# SW6124_A_A_B_C_MCU_SEG.net
KiCad netlist of a schematic drawn in Altium Designer
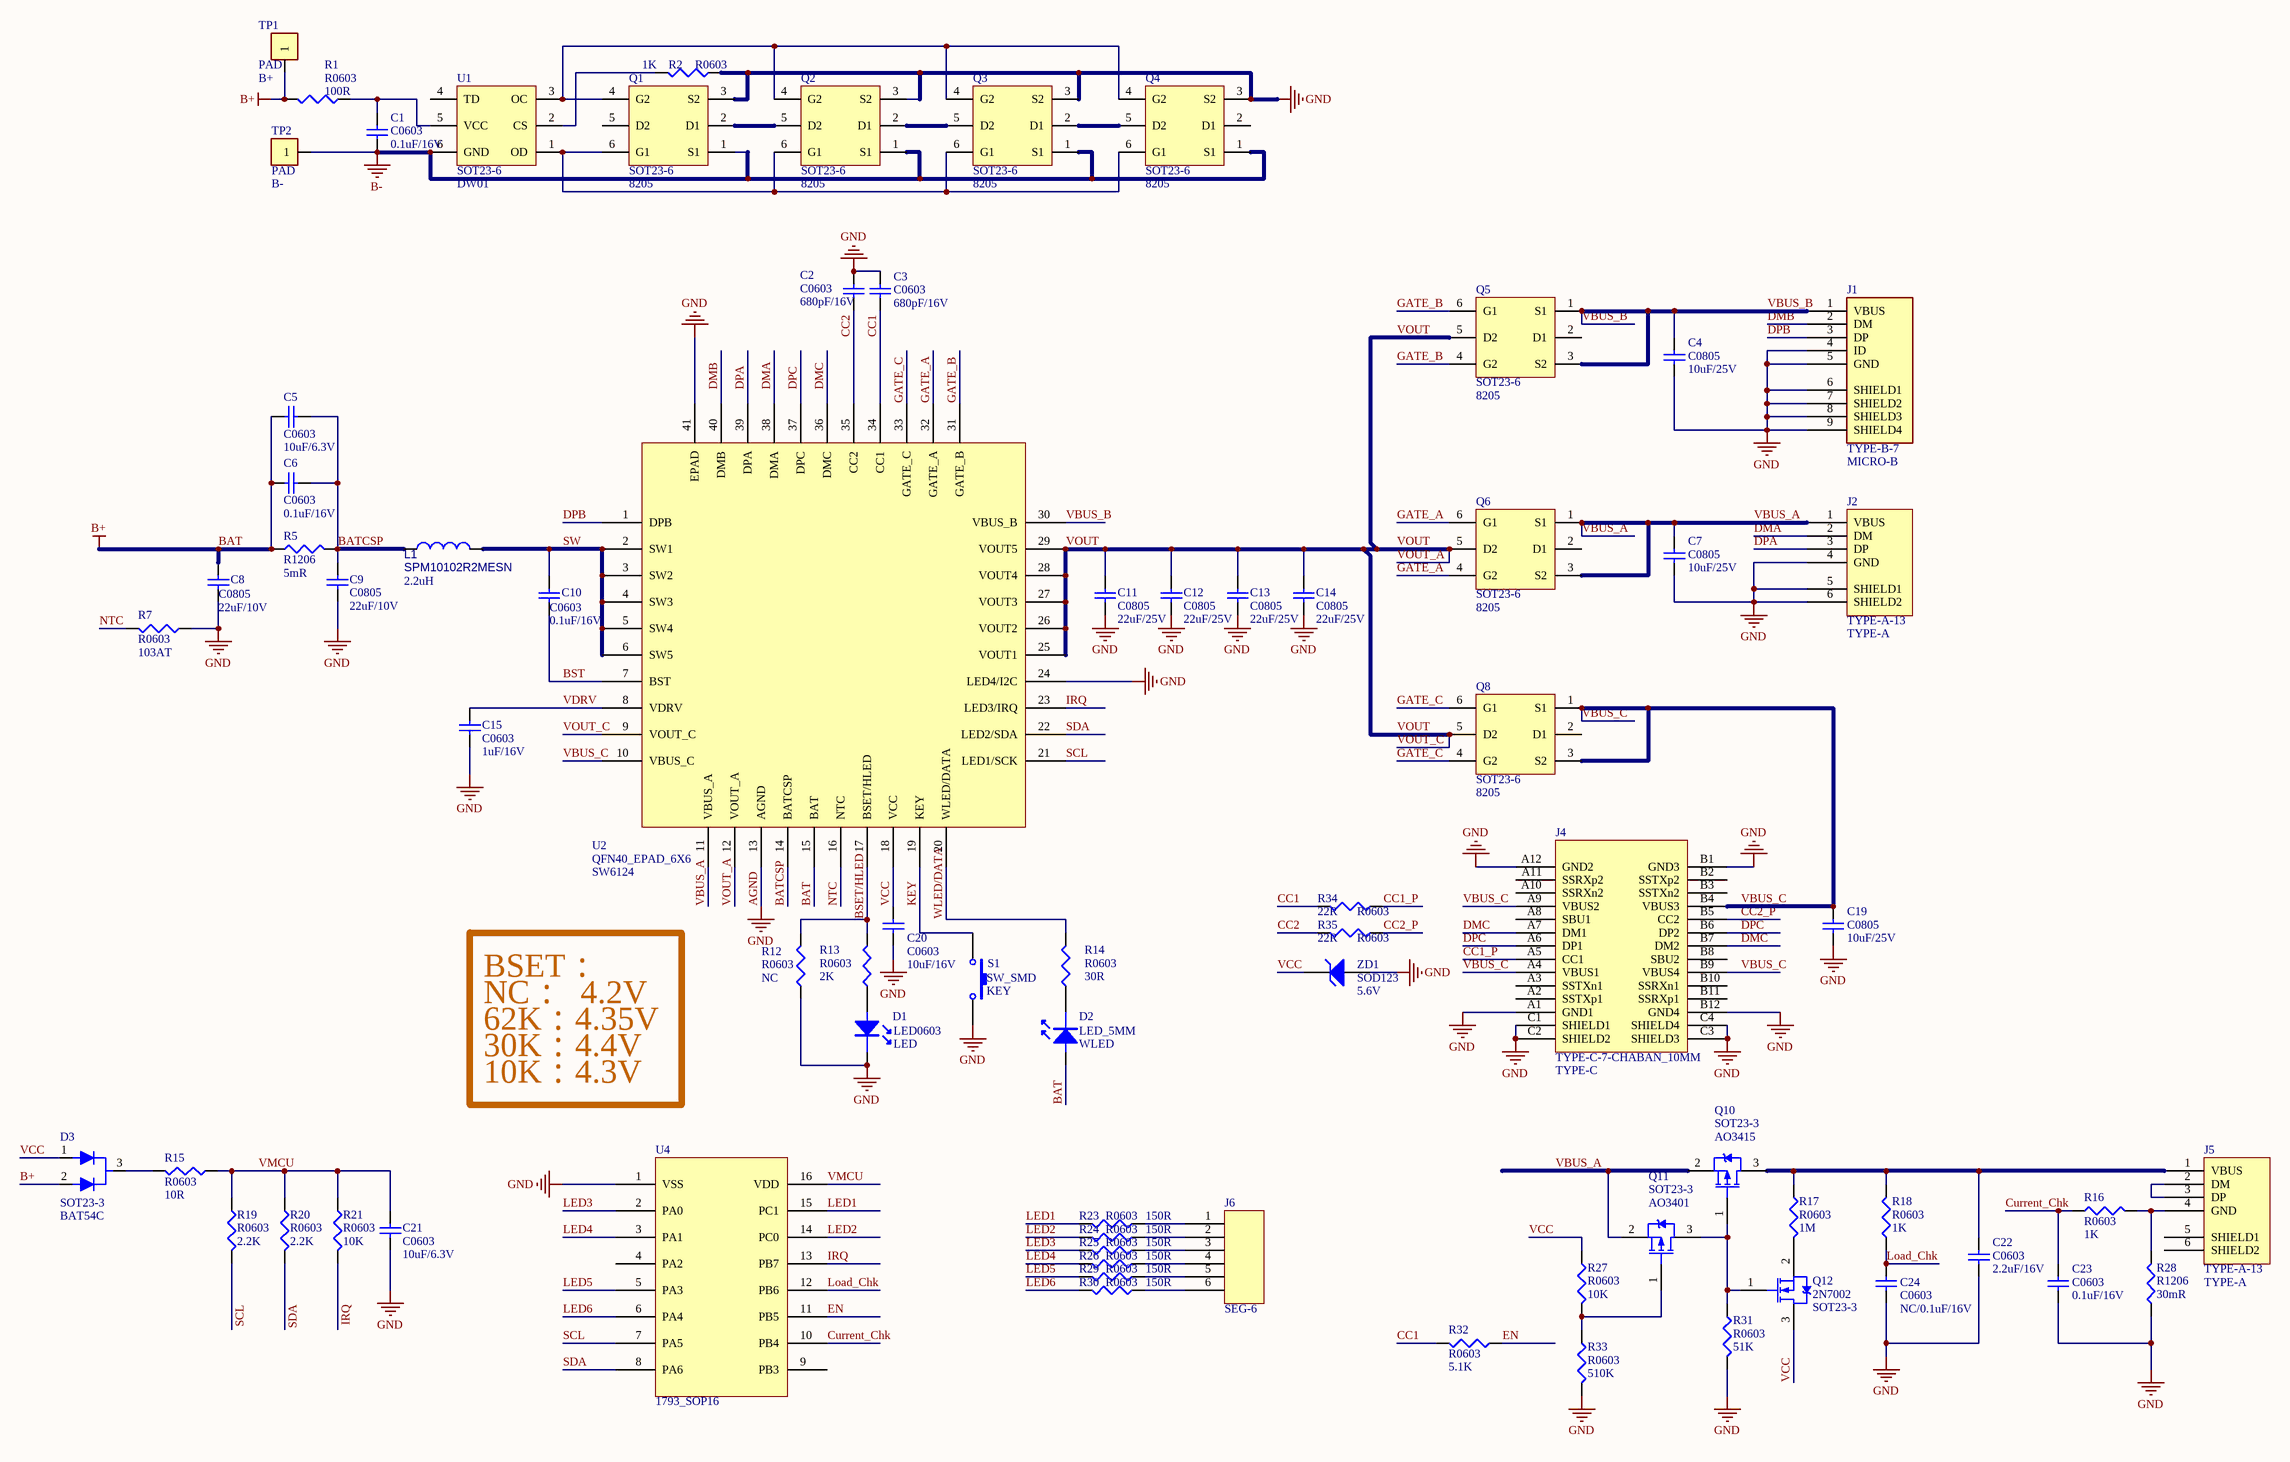
[diagram p0: SW6124+A+A+B+C+MCU+SEG.SchDoc]

(export (version "E")
  (design (tool "Eeschema 10.0.6"))
  (components
    (comp (ref "C1")
      (value "C0603")
      (footprint "C0603")
      (description "Capacitor")
      (fields (field (name "ALTIUM_VALUE") "0.1uF/16V") (field (name "PUBLISHER") "Altium Limited"))
      (libsource (lib "*") (part "Cap"))
    )
    (comp (ref "C2")
      (value "C0603")
      (footprint "C0603")
      (description "Capacitor")
      (fields (field (name "ALTIUM_VALUE") "680pF/16V") (field (name "PUBLISHER") "Altium Limited"))
      (libsource (lib "*") (part "CAP0603"))
    )
    (comp (ref "C3")
      (value "C0603")
      (footprint "C0603")
      (description "Capacitor")
      (fields (field (name "ALTIUM_VALUE") "680pF/16V") (field (name "PUBLISHER") "Altium Limited"))
      (libsource (lib "*") (part "CAP0603"))
    )
    (comp (ref "C4")
      (value "C0805")
      (footprint "C0805")
      (description "Capacitor")
      (fields (field (name "ALTIUM_VALUE") "10uF/25V") (field (name "PUBLISHER") "Altium Limited"))
      (libsource (lib "*") (part "CAP0603"))
    )
    (comp (ref "C5")
      (value "C0603")
      (footprint "C0603")
      (description "Capacitor")
      (fields (field (name "ALTIUM_VALUE") "10uF/6.3V") (field (name "PUBLISHER") "Altium Limited"))
      (libsource (lib "*") (part "CAP0603"))
    )
    (comp (ref "C6")
      (value "C0603")
      (footprint "C0603")
      (description "Capacitor")
      (fields (field (name "ALTIUM_VALUE") "0.1uF/16V") (field (name "PUBLISHER") "Altium Limited"))
      (libsource (lib "*") (part "CAP0603"))
    )
    (comp (ref "C7")
      (value "C0805")
      (footprint "C0805")
      (description "Capacitor")
      (fields (field (name "ALTIUM_VALUE") "10uF/25V") (field (name "PUBLISHER") "Altium Limited"))
      (libsource (lib "*") (part "CAP0603"))
    )
    (comp (ref "C8")
      (value "C0805")
      (footprint "C0805")
      (description "Capacitor")
      (fields (field (name "ALTIUM_VALUE") "22uF/10V") (field (name "PUBLISHER") "Altium Limited"))
      (libsource (lib "*") (part "CAP0805"))
    )
    (comp (ref "C9")
      (value "C0805")
      (footprint "C0805")
      (description "Capacitor")
      (fields (field (name "ALTIUM_VALUE") "22uF/10V") (field (name "PUBLISHER") "Altium Limited"))
      (libsource (lib "*") (part "CAP0805"))
    )
    (comp (ref "C10")
      (value "C0603")
      (footprint "C0603")
      (description "Capacitor")
      (fields (field (name "ALTIUM_VALUE") "0.1uF/16V") (field (name "PUBLISHER") "Altium Limited"))
      (libsource (lib "*") (part "CAP0603"))
    )
    (comp (ref "C11")
      (value "C0805")
      (footprint "C0805")
      (description "Capacitor")
      (fields (field (name "ALTIUM_VALUE") "22uF/25V") (field (name "PUBLISHER") "Altium Limited"))
      (libsource (lib "*") (part "CAP0805"))
    )
    (comp (ref "C12")
      (value "C0805")
      (footprint "C0805")
      (description "Capacitor")
      (fields (field (name "ALTIUM_VALUE") "22uF/25V") (field (name "PUBLISHER") "Altium Limited"))
      (libsource (lib "*") (part "CAP0805"))
    )
    (comp (ref "C13")
      (value "C0805")
      (footprint "C0805")
      (description "Capacitor")
      (fields (field (name "ALTIUM_VALUE") "22uF/25V") (field (name "PUBLISHER") "Altium Limited"))
      (libsource (lib "*") (part "CAP0805"))
    )
    (comp (ref "C14")
      (value "C0805")
      (footprint "C0805")
      (description "Capacitor")
      (fields (field (name "ALTIUM_VALUE") "22uF/25V") (field (name "PUBLISHER") "Altium Limited"))
      (libsource (lib "*") (part "CAP0805"))
    )
    (comp (ref "C15")
      (value "C0603")
      (footprint "C0603")
      (description "Capacitor")
      (fields (field (name "ALTIUM_VALUE") "1uF/16V") (field (name "PUBLISHER") "Altium Limited"))
      (libsource (lib "*") (part "CAP0603"))
    )
    (comp (ref "C19")
      (value "C0805")
      (footprint "C0805")
      (description "Capacitor")
      (fields (field (name "ALTIUM_VALUE") "10uF/25V") (field (name "PUBLISHER") "Altium Limited"))
      (libsource (lib "*") (part "CAP0603"))
    )
    (comp (ref "C20")
      (value "C0603")
      (footprint "C0603")
      (description "Capacitor")
      (fields (field (name "ALTIUM_VALUE") "10uF/16V") (field (name "PUBLISHER") "Altium Limited"))
      (libsource (lib "*") (part "CAP0603"))
    )
    (comp (ref "C21")
      (value "C0603")
      (footprint "C0603")
      (description "Capacitor")
      (fields (field (name "ALTIUM_VALUE") "10uF/6.3V") (field (name "PUBLISHER") "Altium Limited"))
      (libsource (lib "*") (part "CAP0603"))
    )
    (comp (ref "C22")
      (value "C0603")
      (footprint "C0603")
      (description "Capacitor")
      (fields (field (name "ALTIUM_VALUE") "2.2uF/16V") (field (name "PUBLISHER") "Altium Limited"))
      (libsource (lib "*") (part "CAP0603"))
    )
    (comp (ref "C23")
      (value "C0603")
      (footprint "C0603")
      (description "Capacitor")
      (fields (field (name "ALTIUM_VALUE") "0.1uF/16V") (field (name "PUBLISHER") "Altium Limited"))
      (libsource (lib "*") (part "CAP0603"))
    )
    (comp (ref "C24")
      (value "C0603")
      (footprint "C0603")
      (description "Capacitor")
      (fields (field (name "ALTIUM_VALUE") "NC/0.1uF/16V") (field (name "PUBLISHER") "Altium Limited"))
      (libsource (lib "*") (part "CAP0603"))
    )
    (comp (ref "D1") (value "LED") (footprint "LED0603") (libsource (lib "*") (part "LED")))
    (comp (ref "D2")
      (value "WLED")
      (footprint "LED_5MM")
      (fields (field (name "FOOTPRINF") "LED_5MM") (field (name "Comment") "LED_5MM"))
      (libsource (lib "*") (part "LED"))
    )
    (comp (ref "D3") (value "BAT54C") (footprint "SOT23-3") (libsource (lib "Schlib1-2012") (part "D3")))
    (comp (ref "J1")
      (value "MICRO-B")
      (footprint "TYPE-B-7")
      (fields (field (name "FOOTPRINTF") "TYPE-B-7") (field (name "Comment") "USB_MICRO_B"))
      (libsource (lib "*") (part "USB_MICRO_B"))
    )
    (comp (ref "J2")
      (value "TYPE-A")
      (footprint "TYPE-A-13")
      (fields (field (name "FOOTPRINF") "TYPE-A-13") (field (name "Comment") "TYPE-A-1"))
      (libsource (lib "*") (part "TYPE-A-1"))
    )
    (comp (ref "J4")
      (value "TYPE-C")
      (footprint "TYPE-C-7-CHABAN_10MM")
      (libsource (lib "*") (part "TYPE-C"))
    )
    (comp (ref "J5")
      (value "TYPE-A")
      (footprint "PIE10-USB")
      (fields (field (name "FOOTPRINF") "TYPE-A-13") (field (name "Comment") "TYPE-A-1"))
      (libsource (lib "*") (part "TYPE-A-1"))
    )
    (comp (ref "J6") (value "SEG-6") (libsource (lib "TEST") (part "LCD-6")))
    (comp (ref "L1")
      (value "SPM10102R2MESN")
      (footprint "INDUCTOR_SPM1010")
      (fields (field (name "ALTIUM_VALUE") "2.2uH"))
      (libsource (lib "*") (part "INDUCTOR"))
    )
    (comp (ref "Q1")
      (value "8205")
      (footprint "SOT23-6")
      (fields (field (name "FOOTPRINF") "SOT23-6"))
      (libsource (lib "") (part "8205B_1"))
    )
    (comp (ref "Q2")
      (value "8205")
      (footprint "SOT23-6")
      (fields (field (name "FOOTPRINF") "SOT23-6"))
      (libsource (lib "") (part "8205B_1"))
    )
    (comp (ref "Q3")
      (value "8205")
      (footprint "SOT23-6")
      (fields (field (name "FOOTPRINF") "SOT23-6"))
      (libsource (lib "") (part "8205B_1"))
    )
    (comp (ref "Q4")
      (value "8205")
      (footprint "SOT23-6")
      (fields (field (name "FOOTPRINF") "SOT23-6"))
      (libsource (lib "") (part "8205B_1"))
    )
    (comp (ref "Q5")
      (value "8205")
      (footprint "SOT23-6")
      (fields (field (name "FOOTPRINF") "SOT23-6"))
      (libsource (lib "*") (part "8205B"))
    )
    (comp (ref "Q6")
      (value "8205")
      (footprint "SOT23-6")
      (fields (field (name "FOOTPRINF") "SOT23-6"))
      (libsource (lib "*") (part "8205B"))
    )
    (comp (ref "Q8")
      (value "8205")
      (footprint "SOT23-6")
      (fields (field (name "FOOTPRINF") "SOT23-6"))
      (libsource (lib "*") (part "8205B"))
    )
    (comp (ref "Q10")
      (value "AO3415")
      (footprint "SOT23-3")
      (description "P-Channel Power MOSFET")
      (fields (field (name "Comment") "PMOS-2") (field (name "PUBLISHER") "Altium Limited"))
      (libsource (lib "Miscellaneous Devices") (part "PMOS-2"))
    )
    (comp (ref "Q11")
      (value "AO3401")
      (footprint "SOT23-3")
      (description "P-Channel Power MOSFET")
      (fields (field (name "Comment") "PMOS-2") (field (name "PUBLISHER") "Altium Limited"))
      (libsource (lib "Miscellaneous Devices") (part "PMOS-2"))
    )
    (comp (ref "Q12")
      (value "2N7002")
      (footprint "SOT23-3")
      (description "N-Channel Power MOSFET")
      (fields (field (name "Comment") "NMOS-2") (field (name "PUBLISHER") "Altium Limited"))
      (libsource (lib "Miscellaneous Devices") (part "NMOS-2"))
    )
    (comp (ref "R1")
      (value "R0603")
      (footprint "R0603")
      (description "Resistor")
      (fields (field (name "ALTIUM_VALUE") "100R") (field (name "PUBLISHER") "Altium Limited"))
      (libsource (lib "*") (part "Res3"))
    )
    (comp (ref "R2")
      (value "R0603")
      (footprint "R0603")
      (description "Resistor")
      (fields (field (name "ALTIUM_VALUE") "1K") (field (name "PUBLISHER") "Altium Limited"))
      (libsource (lib "*") (part "Res3"))
    )
    (comp (ref "R5")
      (value "R1206")
      (footprint "R1206")
      (description "Resistor")
      (fields (field (name "ALTIUM_VALUE") "5mR") (field (name "PUBLISHER") "Altium Limited"))
      (libsource (lib "*") (part "RES"))
    )
    (comp (ref "R7")
      (value "R0603")
      (footprint "R0603")
      (description "Resistor")
      (fields (field (name "ALTIUM_VALUE") "103AT") (field (name "PUBLISHER") "Altium Limited"))
      (libsource (lib "*") (part "RES"))
    )
    (comp (ref "R12")
      (value "R0603")
      (footprint "R0603")
      (description "Resistor")
      (fields (field (name "ALTIUM_VALUE") "NC") (field (name "PUBLISHER") "Altium Limited"))
      (libsource (lib "*") (part "RES"))
    )
    (comp (ref "R13")
      (value "R0603")
      (footprint "R0603")
      (description "Resistor")
      (fields (field (name "ALTIUM_VALUE") "2K") (field (name "PUBLISHER") "Altium Limited"))
      (libsource (lib "*") (part "RES"))
    )
    (comp (ref "R14")
      (value "R0603")
      (footprint "R0603")
      (description "Resistor")
      (fields (field (name "ALTIUM_VALUE") "30R") (field (name "PUBLISHER") "Altium Limited"))
      (libsource (lib "*") (part "RES"))
    )
    (comp (ref "R15")
      (value "R0603")
      (footprint "R0603")
      (description "Resistor")
      (fields (field (name "ALTIUM_VALUE") "10R") (field (name "PUBLISHER") "Altium Limited"))
      (libsource (lib "*") (part "RES"))
    )
    (comp (ref "R16")
      (value "R0603")
      (footprint "R0603")
      (description "Resistor")
      (fields (field (name "ALTIUM_VALUE") "1K") (field (name "PUBLISHER") "Altium Limited"))
      (libsource (lib "*") (part "RES"))
    )
    (comp (ref "R17")
      (value "R0603")
      (footprint "R0603")
      (description "Resistor")
      (fields (field (name "ALTIUM_VALUE") "1M") (field (name "PUBLISHER") "Altium Limited"))
      (libsource (lib "*") (part "RES"))
    )
    (comp (ref "R18")
      (value "R0603")
      (footprint "R0603")
      (description "Resistor")
      (fields (field (name "ALTIUM_VALUE") "1K") (field (name "PUBLISHER") "Altium Limited"))
      (libsource (lib "*") (part "RES"))
    )
    (comp (ref "R19")
      (value "R0603")
      (footprint "R0603")
      (description "Resistor")
      (fields (field (name "ALTIUM_VALUE") "2.2K") (field (name "PUBLISHER") "Altium Limited"))
      (libsource (lib "*") (part "RES"))
    )
    (comp (ref "R20")
      (value "R0603")
      (footprint "R0603")
      (description "Resistor")
      (fields (field (name "ALTIUM_VALUE") "2.2K") (field (name "PUBLISHER") "Altium Limited"))
      (libsource (lib "*") (part "RES"))
    )
    (comp (ref "R21")
      (value "R0603")
      (footprint "R0603")
      (description "Resistor")
      (fields (field (name "ALTIUM_VALUE") "10K") (field (name "PUBLISHER") "Altium Limited"))
      (libsource (lib "*") (part "RES"))
    )
    (comp (ref "R23")
      (value "R0603")
      (footprint "R0603")
      (description "Resistor")
      (fields (field (name "ALTIUM_VALUE") "150R") (field (name "PUBLISHER") "Altium Limited"))
      (libsource (lib "*") (part "RES"))
    )
    (comp (ref "R24")
      (value "R0603")
      (footprint "R0603")
      (description "Resistor")
      (fields (field (name "ALTIUM_VALUE") "150R") (field (name "PUBLISHER") "Altium Limited"))
      (libsource (lib "*") (part "RES"))
    )
    (comp (ref "R25")
      (value "R0603")
      (footprint "R0603")
      (description "Resistor")
      (fields (field (name "ALTIUM_VALUE") "150R") (field (name "PUBLISHER") "Altium Limited"))
      (libsource (lib "*") (part "RES"))
    )
    (comp (ref "R26")
      (value "R0603")
      (footprint "R0603")
      (description "Resistor")
      (fields (field (name "ALTIUM_VALUE") "150R") (field (name "PUBLISHER") "Altium Limited"))
      (libsource (lib "*") (part "RES"))
    )
    (comp (ref "R27")
      (value "R0603")
      (footprint "R0603")
      (description "Resistor")
      (fields (field (name "ALTIUM_VALUE") "10K") (field (name "PUBLISHER") "Altium Limited"))
      (libsource (lib "*") (part "RES"))
    )
    (comp (ref "R28")
      (value "R1206")
      (footprint "C-1206A")
      (description "Resistor")
      (fields (field (name "ALTIUM_VALUE") "30mR") (field (name "PUBLISHER") "Altium Limited"))
      (libsource (lib "*") (part "RES"))
    )
    (comp (ref "R29")
      (value "R0603")
      (footprint "R0603")
      (description "Resistor")
      (fields (field (name "ALTIUM_VALUE") "150R") (field (name "PUBLISHER") "Altium Limited"))
      (libsource (lib "*") (part "RES"))
    )
    (comp (ref "R30")
      (value "R0603")
      (footprint "R0603")
      (description "Resistor")
      (fields (field (name "ALTIUM_VALUE") "150R") (field (name "PUBLISHER") "Altium Limited"))
      (libsource (lib "*") (part "RES"))
    )
    (comp (ref "R31")
      (value "R0603")
      (footprint "R0603")
      (description "Resistor")
      (fields (field (name "ALTIUM_VALUE") "51K") (field (name "PUBLISHER") "Altium Limited"))
      (libsource (lib "*") (part "RES"))
    )
    (comp (ref "R32")
      (value "R0603")
      (footprint "R0603")
      (description "Resistor")
      (fields (field (name "ALTIUM_VALUE") "5.1K") (field (name "PUBLISHER") "Altium Limited"))
      (libsource (lib "*") (part "RES"))
    )
    (comp (ref "R33")
      (value "R0603")
      (footprint "R0603")
      (description "Resistor")
      (fields (field (name "ALTIUM_VALUE") "510K") (field (name "PUBLISHER") "Altium Limited"))
      (libsource (lib "*") (part "RES"))
    )
    (comp (ref "R34")
      (value "R0603")
      (footprint "R0603")
      (description "Resistor")
      (fields (field (name "ALTIUM_VALUE") "22R") (field (name "PUBLISHER") "Altium Limited"))
      (libsource (lib "*") (part "RES"))
    )
    (comp (ref "R35")
      (value "R0603")
      (footprint "R0603")
      (description "Resistor")
      (fields (field (name "ALTIUM_VALUE") "22R") (field (name "PUBLISHER") "Altium Limited"))
      (libsource (lib "*") (part "RES"))
    )
    (comp (ref "S1")
      (value "KEY")
      (footprint "SW_SMD")
      (fields (field (name "FOOTPRINF") "SW_SMD"))
      (libsource (lib "*") (part "SW K"))
    )
    (comp (ref "TP1") (value "B+") (footprint "PAD") (libsource (lib "") (part "Test Point_1")))
    (comp (ref "TP2") (value "B-") (footprint "PAD") (libsource (lib "*") (part "Test Point")))
    (comp (ref "U1")
      (value "DW01")
      (footprint "SOT23-6")
      (fields (field (name "FOOTPRINF") "SOT23-6"))
      (libsource (lib "*") (part "DW01"))
    )
    (comp (ref "U2")
      (value "SW6124")
      (footprint "QFN40_EPAD_6X6")
      (libsource (lib "TEST") (part "SW6106_AFC"))
    )
    (comp (ref "U4") (value "1793_SOP16") (libsource (lib "TEST") (part "1793_SOP16")))
    (comp (ref "ZD1")
      (value "SOD123")
      (footprint "SOD-123")
      (description "Zener Diode")
      (fields (field (name "ALTIUM_UNNAMED_1") "5.6V"))
      (libsource (lib "Miscellaneous Devices") (part "D Zener"))
    )
  )
  (nets
    (net (code "1") (name "/BATCSP") (class "Default")
      (node (ref "C5") (pin "2") (pinfunction "2_2") (pintype "passive"))
      (node (ref "C6") (pin "2") (pinfunction "2_2") (pintype "passive"))
      (node (ref "C9") (pin "2") (pinfunction "2_2") (pintype "passive"))
      (node (ref "L1") (pin "1") (pinfunction "1_1") (pintype "passive"))
      (node (ref "R5") (pin "2") (pinfunction "2_2") (pintype "passive"))
      (node (ref "U2") (pin "14") (pinfunction "BATCSP_14") (pintype "passive"))
    )
    (net (code "2") (name "/BSET{slash}HLED") (class "Default")
      (node (ref "R12") (pin "2") (pinfunction "2_2") (pintype "passive"))
      (node (ref "R13") (pin "2") (pinfunction "2_2") (pintype "passive"))
      (node (ref "U2") (pin "17") (pinfunction "BSET/HLED_17") (pintype "passive"))
    )
    (net (code "3") (name "/BST") (class "Default")
      (node (ref "C10") (pin "1") (pinfunction "1_1") (pintype "passive"))
      (node (ref "U2") (pin "7") (pinfunction "BST_7") (pintype "passive"))
    )
    (net (code "4") (name "/CC1") (class "Default")
      (node (ref "C3") (pin "1") (pinfunction "1_1") (pintype "passive"))
      (node (ref "R32") (pin "2") (pinfunction "2_2") (pintype "passive"))
      (node (ref "R34") (pin "2") (pinfunction "2_2") (pintype "passive"))
      (node (ref "U2") (pin "34") (pinfunction "CC1_34") (pintype "passive"))
    )
    (net (code "5") (name "/CC1_P") (class "Default")
      (node (ref "J4") (pin "A5") (pinfunction "CC1_A5") (pintype "passive"))
      (node (ref "R34") (pin "1") (pinfunction "1_1") (pintype "passive"))
    )
    (net (code "6") (name "/CC2") (class "Default")
      (node (ref "C2") (pin "1") (pinfunction "1_1") (pintype "passive"))
      (node (ref "R35") (pin "2") (pinfunction "2_2") (pintype "passive"))
      (node (ref "U2") (pin "35") (pinfunction "CC2_35") (pintype "passive"))
    )
    (net (code "7") (name "/CC2_P") (class "Default")
      (node (ref "J4") (pin "B5") (pinfunction "CC2_B5") (pintype "passive"))
      (node (ref "R35") (pin "1") (pinfunction "1_1") (pintype "passive"))
    )
    (net (code "8") (name "/Current_Chk") (class "Default")
      (node (ref "C23") (pin "2") (pinfunction "2_2") (pintype "passive"))
      (node (ref "R16") (pin "1") (pinfunction "1_1") (pintype "passive"))
      (node (ref "U4") (pin "10") (pinfunction "PB4_10") (pintype "passive"))
    )
    (net (code "9") (name "/DMA") (class "Default")
      (node (ref "J2") (pin "2") (pinfunction "DM_2") (pintype "passive"))
      (node (ref "U2") (pin "38") (pinfunction "DMA_38") (pintype "passive"))
    )
    (net (code "10") (name "/DMB") (class "Default")
      (node (ref "J1") (pin "2") (pinfunction "DM_2") (pintype "passive"))
      (node (ref "U2") (pin "40") (pinfunction "DMB_40") (pintype "passive"))
    )
    (net (code "11") (name "/DMC") (class "Default")
      (node (ref "J4") (pin "A7") (pinfunction "DM1_A7") (pintype "passive"))
      (node (ref "J4") (pin "B7") (pinfunction "DM2_B7") (pintype "passive"))
      (node (ref "U2") (pin "36") (pinfunction "DMC_36") (pintype "passive"))
    )
    (net (code "12") (name "/DPA") (class "Default")
      (node (ref "J2") (pin "3") (pinfunction "DP_3") (pintype "passive"))
      (node (ref "U2") (pin "39") (pinfunction "DPA_39") (pintype "passive"))
    )
    (net (code "13") (name "/DPB") (class "Default")
      (node (ref "J1") (pin "3") (pinfunction "DP_3") (pintype "passive"))
      (node (ref "U2") (pin "1") (pinfunction "DPB_1") (pintype "passive"))
    )
    (net (code "14") (name "/DPC") (class "Default")
      (node (ref "J4") (pin "A6") (pinfunction "DP1_A6") (pintype "passive"))
      (node (ref "J4") (pin "B6") (pinfunction "DP2_B6") (pintype "passive"))
      (node (ref "U2") (pin "37") (pinfunction "DPC_37") (pintype "passive"))
    )
    (net (code "15") (name "/EN") (class "Default")
      (node (ref "R32") (pin "1") (pinfunction "1_1") (pintype "passive"))
      (node (ref "U4") (pin "11") (pinfunction "PB5_11") (pintype "passive"))
    )
    (net (code "16") (name "/GATE_A") (class "Default")
      (node (ref "Q6") (pin "4") (pinfunction "G2_4") (pintype "passive"))
      (node (ref "Q6") (pin "6") (pinfunction "G1_6") (pintype "passive"))
      (node (ref "U2") (pin "32") (pinfunction "GATE_A_32") (pintype "passive"))
    )
    (net (code "17") (name "/GATE_B") (class "Default")
      (node (ref "Q5") (pin "4") (pinfunction "G2_4") (pintype "passive"))
      (node (ref "Q5") (pin "6") (pinfunction "G1_6") (pintype "passive"))
      (node (ref "U2") (pin "31") (pinfunction "GATE_B_31") (pintype "passive"))
    )
    (net (code "18") (name "/GATE_C") (class "Default")
      (node (ref "Q8") (pin "4") (pinfunction "G2_4") (pintype "passive"))
      (node (ref "Q8") (pin "6") (pinfunction "G1_6") (pintype "passive"))
      (node (ref "U2") (pin "33") (pinfunction "GATE_C_33") (pintype "passive"))
    )
    (net (code "19") (name "/IRQ") (class "Default")
      (node (ref "R21") (pin "2") (pinfunction "2_2") (pintype "passive"))
      (node (ref "U2") (pin "23") (pinfunction "LED3/IRQ_23") (pintype "passive"))
      (node (ref "U4") (pin "13") (pinfunction "PB7_13") (pintype "passive"))
    )
    (net (code "20") (name "/KEY") (class "Default")
      (node (ref "S1") (pin "1") (pinfunction "1_1") (pintype "passive"))
      (node (ref "U2") (pin "19") (pinfunction "KEY_19") (pintype "passive"))
    )
    (net (code "21") (name "/LED1") (class "Default")
      (node (ref "R23") (pin "2") (pinfunction "2_2") (pintype "passive"))
      (node (ref "U4") (pin "15") (pinfunction "PC1_15") (pintype "passive"))
    )
    (net (code "22") (name "/LED2") (class "Default")
      (node (ref "R24") (pin "2") (pinfunction "2_2") (pintype "passive"))
      (node (ref "U4") (pin "14") (pinfunction "PC0_14") (pintype "passive"))
    )
    (net (code "23") (name "/LED3") (class "Default")
      (node (ref "R25") (pin "2") (pinfunction "2_2") (pintype "passive"))
      (node (ref "U4") (pin "2") (pinfunction "PA0_2") (pintype "passive"))
    )
    (net (code "24") (name "/LED4") (class "Default")
      (node (ref "R26") (pin "2") (pinfunction "2_2") (pintype "passive"))
      (node (ref "U4") (pin "3") (pinfunction "PA1_3") (pintype "passive"))
    )
    (net (code "25") (name "/LED5") (class "Default")
      (node (ref "R29") (pin "2") (pinfunction "2_2") (pintype "passive"))
      (node (ref "U4") (pin "5") (pinfunction "PA3_5") (pintype "passive"))
    )
    (net (code "26") (name "/LED6") (class "Default")
      (node (ref "R30") (pin "2") (pinfunction "2_2") (pintype "passive"))
      (node (ref "U4") (pin "6") (pinfunction "PA4_6") (pintype "passive"))
    )
    (net (code "27") (name "/Load_Chk") (class "Default")
      (node (ref "C24") (pin "2") (pinfunction "2_2") (pintype "passive"))
      (node (ref "R18") (pin "1") (pinfunction "1_1") (pintype "passive"))
      (node (ref "U4") (pin "12") (pinfunction "PB6_12") (pintype "passive"))
    )
    (net (code "28") (name "/NTC") (class "Default")
      (node (ref "R7") (pin "2") (pinfunction "2_2") (pintype "passive"))
      (node (ref "U2") (pin "16") (pinfunction "NTC_16") (pintype "passive"))
    )
    (net (code "29") (name "/SCL") (class "Default")
      (node (ref "R19") (pin "2") (pinfunction "2_2") (pintype "passive"))
      (node (ref "U2") (pin "21") (pinfunction "LED1/SCK_21") (pintype "passive"))
      (node (ref "U4") (pin "7") (pinfunction "PA5_7") (pintype "passive"))
    )
    (net (code "30") (name "/SDA") (class "Default")
      (node (ref "R20") (pin "2") (pinfunction "2_2") (pintype "passive"))
      (node (ref "U2") (pin "22") (pinfunction "LED2/SDA_22") (pintype "passive"))
      (node (ref "U4") (pin "8") (pinfunction "PA6_8") (pintype "passive"))
    )
    (net (code "31") (name "/SW") (class "Default")
      (node (ref "C10") (pin "2") (pinfunction "2_2") (pintype "passive"))
      (node (ref "L1") (pin "2") (pinfunction "2_2") (pintype "passive"))
      (node (ref "U2") (pin "2") (pinfunction "SW1_2") (pintype "passive"))
      (node (ref "U2") (pin "3") (pinfunction "SW2_3") (pintype "passive"))
      (node (ref "U2") (pin "4") (pinfunction "SW3_4") (pintype "passive"))
      (node (ref "U2") (pin "5") (pinfunction "SW4_5") (pintype "passive"))
      (node (ref "U2") (pin "6") (pinfunction "SW5_6") (pintype "passive"))
    )
    (net (code "32") (name "/VBUS_A") (class "Default")
      (node (ref "C7") (pin "2") (pinfunction "2_2") (pintype "passive"))
      (node (ref "J2") (pin "1") (pinfunction "VBUS_1") (pintype "passive"))
      (node (ref "Q10") (pin "2") (pinfunction "S_2") (pintype "passive"))
      (node (ref "Q11") (pin "2") (pinfunction "S_2") (pintype "passive"))
      (node (ref "Q6") (pin "1") (pinfunction "S1_1") (pintype "passive"))
      (node (ref "Q6") (pin "3") (pinfunction "S2_3") (pintype "passive"))
      (node (ref "U2") (pin "11") (pinfunction "VBUS_A_11") (pintype "passive"))
    )
    (net (code "33") (name "/VBUS_B") (class "Default")
      (node (ref "C4") (pin "2") (pinfunction "2_2") (pintype "passive"))
      (node (ref "J1") (pin "1") (pinfunction "VBUS_1") (pintype "passive"))
      (node (ref "Q5") (pin "1") (pinfunction "S1_1") (pintype "passive"))
      (node (ref "Q5") (pin "3") (pinfunction "S2_3") (pintype "passive"))
      (node (ref "U2") (pin "30") (pinfunction "VBUS_B_30") (pintype "passive"))
    )
    (net (code "34") (name "/VBUS_C") (class "Default")
      (node (ref "C19") (pin "2") (pinfunction "2_2") (pintype "passive"))
      (node (ref "J4") (pin "A4") (pinfunction "VBUS1_A4") (pintype "passive"))
      (node (ref "J4") (pin "A9") (pinfunction "VBUS2_A9") (pintype "passive"))
      (node (ref "J4") (pin "B4") (pinfunction "VBUS3_B4") (pintype "passive"))
      (node (ref "J4") (pin "B9") (pinfunction "VBUS4_B9") (pintype "passive"))
      (node (ref "Q8") (pin "1") (pinfunction "S1_1") (pintype "passive"))
      (node (ref "Q8") (pin "3") (pinfunction "S2_3") (pintype "passive"))
      (node (ref "U2") (pin "10") (pinfunction "VBUS_C_10") (pintype "passive"))
    )
    (net (code "35") (name "/VCC") (class "Default")
      (node (ref "C20") (pin "2") (pinfunction "2_2") (pintype "passive"))
      (node (ref "D3") (pin "1") (pintype "passive"))
      (node (ref "Q12") (pin "3") (pinfunction "D_3") (pintype "passive"))
      (node (ref "R27") (pin "1") (pinfunction "1_1") (pintype "passive"))
      (node (ref "U2") (pin "18") (pinfunction "VCC_18") (pintype "passive"))
      (node (ref "ZD1") (pin "2") (pinfunction "K_2") (pintype "passive"))
    )
    (net (code "36") (name "/VDRV") (class "Default")
      (node (ref "C15") (pin "2") (pinfunction "2_2") (pintype "passive"))
      (node (ref "U2") (pin "8") (pinfunction "VDRV_8") (pintype "passive"))
    )
    (net (code "37") (name "/VMCU") (class "Default")
      (node (ref "C21") (pin "1") (pinfunction "1_1") (pintype "passive"))
      (node (ref "R15") (pin "1") (pinfunction "1_1") (pintype "passive"))
      (node (ref "R19") (pin "1") (pinfunction "1_1") (pintype "passive"))
      (node (ref "R20") (pin "1") (pinfunction "1_1") (pintype "passive"))
      (node (ref "R21") (pin "1") (pinfunction "1_1") (pintype "passive"))
      (node (ref "U4") (pin "16") (pinfunction "VDD_16") (pintype "passive"))
    )
    (net (code "38") (name "/VOUT") (class "Default")
      (node (ref "C11") (pin "2") (pinfunction "2_2") (pintype "passive"))
      (node (ref "C12") (pin "2") (pinfunction "2_2") (pintype "passive"))
      (node (ref "C13") (pin "2") (pinfunction "2_2") (pintype "passive"))
      (node (ref "C14") (pin "2") (pinfunction "2_2") (pintype "passive"))
      (node (ref "Q5") (pin "5") (pinfunction "D2_5") (pintype "passive"))
      (node (ref "Q6") (pin "5") (pinfunction "D2_5") (pintype "passive"))
      (node (ref "Q8") (pin "5") (pinfunction "D2_5") (pintype "passive"))
      (node (ref "U2") (pin "12") (pinfunction "VOUT_A_12") (pintype "passive"))
      (node (ref "U2") (pin "25") (pinfunction "VOUT1_25") (pintype "passive"))
      (node (ref "U2") (pin "26") (pinfunction "VOUT2_26") (pintype "passive"))
      (node (ref "U2") (pin "27") (pinfunction "VOUT3_27") (pintype "passive"))
      (node (ref "U2") (pin "28") (pinfunction "VOUT4_28") (pintype "passive"))
      (node (ref "U2") (pin "29") (pinfunction "VOUT5_29") (pintype "passive"))
      (node (ref "U2") (pin "9") (pinfunction "VOUT_C_9") (pintype "passive"))
    )
    (net (code "39") (name "/WLED{slash}DATA") (class "Default")
      (node (ref "R14") (pin "2") (pinfunction "2_2") (pintype "passive"))
      (node (ref "U2") (pin "20") (pinfunction "WLED/DATA_20") (pintype "passive"))
    )
    (net (code "40") (name "B+") (class "Default")
      (node (ref "C5") (pin "1") (pinfunction "1_1") (pintype "passive"))
      (node (ref "C6") (pin "1") (pinfunction "1_1") (pintype "passive"))
      (node (ref "C8") (pin "2") (pinfunction "2_2") (pintype "passive"))
      (node (ref "D2") (pin "1") (pinfunction "A_1") (pintype "passive"))
      (node (ref "D3") (pin "2") (pintype "passive"))
      (node (ref "R1") (pin "2") (pinfunction "2_2") (pintype "passive"))
      (node (ref "R5") (pin "1") (pinfunction "1_1") (pintype "passive"))
      (node (ref "TP1") (pin "1") (pinfunction "1_1") (pintype "passive"))
      (node (ref "U2") (pin "15") (pinfunction "BAT_15") (pintype "passive"))
    )
    (net (code "41") (name "B-") (class "Default")
      (node (ref "C1") (pin "1") (pinfunction "1_1") (pintype "passive"))
      (node (ref "Q1") (pin "1") (pinfunction "S1_1") (pintype "passive"))
      (node (ref "Q2") (pin "1") (pinfunction "S1_1") (pintype "passive"))
      (node (ref "Q3") (pin "1") (pinfunction "S1_1") (pintype "passive"))
      (node (ref "Q4") (pin "1") (pinfunction "S1_1") (pintype "passive"))
      (node (ref "TP2") (pin "1") (pinfunction "1_1") (pintype "passive"))
      (node (ref "U1") (pin "6") (pinfunction "GND_6") (pintype "passive"))
    )
    (net (code "42") (name "GND") (class "Default")
      (node (ref "C11") (pin "1") (pinfunction "1_1") (pintype "passive"))
      (node (ref "C12") (pin "1") (pinfunction "1_1") (pintype "passive"))
      (node (ref "C13") (pin "1") (pinfunction "1_1") (pintype "passive"))
      (node (ref "C14") (pin "1") (pinfunction "1_1") (pintype "passive"))
      (node (ref "C15") (pin "1") (pinfunction "1_1") (pintype "passive"))
      (node (ref "C19") (pin "1") (pinfunction "1_1") (pintype "passive"))
      (node (ref "C2") (pin "2") (pinfunction "2_2") (pintype "passive"))
      (node (ref "C20") (pin "1") (pinfunction "1_1") (pintype "passive"))
      (node (ref "C21") (pin "2") (pinfunction "2_2") (pintype "passive"))
      (node (ref "C22") (pin "1") (pinfunction "1_1") (pintype "passive"))
      (node (ref "C23") (pin "1") (pinfunction "1_1") (pintype "passive"))
      (node (ref "C24") (pin "1") (pinfunction "1_1") (pintype "passive"))
      (node (ref "C3") (pin "2") (pinfunction "2_2") (pintype "passive"))
      (node (ref "C4") (pin "1") (pinfunction "1_1") (pintype "passive"))
      (node (ref "C7") (pin "1") (pinfunction "1_1") (pintype "passive"))
      (node (ref "C8") (pin "1") (pinfunction "1_1") (pintype "passive"))
      (node (ref "C9") (pin "1") (pinfunction "1_1") (pintype "passive"))
      (node (ref "D1") (pin "2") (pinfunction "K_2") (pintype "passive"))
      (node (ref "J1") (pin "4") (pinfunction "ID_4") (pintype "passive"))
      (node (ref "J1") (pin "5") (pinfunction "GND_5") (pintype "passive"))
      (node (ref "J1") (pin "6") (pinfunction "SHIELD1_6") (pintype "passive"))
      (node (ref "J1") (pin "7") (pinfunction "SHIELD2_7") (pintype "passive"))
      (node (ref "J1") (pin "8") (pinfunction "SHIELD3_8") (pintype "passive"))
      (node (ref "J1") (pin "9") (pinfunction "SHIELD4_9") (pintype "passive"))
      (node (ref "J2") (pin "4") (pinfunction "GND_4") (pintype "passive"))
      (node (ref "J2") (pin "5") (pinfunction "SHIELD1_5") (pintype "passive"))
      (node (ref "J2") (pin "6") (pinfunction "SHIELD2_6") (pintype "passive"))
      (node (ref "J4") (pin "A1") (pinfunction "GND1_A1") (pintype "passive"))
      (node (ref "J4") (pin "A12") (pinfunction "GND2_A12") (pintype "passive"))
      (node (ref "J4") (pin "B1") (pinfunction "GND3_B1") (pintype "passive"))
      (node (ref "J4") (pin "B12") (pinfunction "GND4_B12") (pintype "passive"))
      (node (ref "J4") (pin "C1") (pinfunction "SHIELD1_C1") (pintype "passive"))
      (node (ref "J4") (pin "C2") (pinfunction "SHIELD2_C2") (pintype "passive"))
      (node (ref "J4") (pin "C3") (pinfunction "SHIELD3_C3") (pintype "passive"))
      (node (ref "J4") (pin "C4") (pinfunction "SHIELD4_C4") (pintype "passive"))
      (node (ref "Q1") (pin "3") (pinfunction "S2_3") (pintype "passive"))
      (node (ref "Q2") (pin "3") (pinfunction "S2_3") (pintype "passive"))
      (node (ref "Q3") (pin "3") (pinfunction "S2_3") (pintype "passive"))
      (node (ref "Q4") (pin "3") (pinfunction "S2_3") (pintype "passive"))
      (node (ref "R12") (pin "1") (pinfunction "1_1") (pintype "passive"))
      (node (ref "R2") (pin "1") (pinfunction "1_1") (pintype "passive"))
      (node (ref "R28") (pin "1") (pinfunction "1_1") (pintype "passive"))
      (node (ref "R31") (pin "2") (pinfunction "2_2") (pintype "passive"))
      (node (ref "R33") (pin "2") (pinfunction "2_2") (pintype "passive"))
      (node (ref "R7") (pin "1") (pinfunction "1_1") (pintype "passive"))
      (node (ref "S1") (pin "2") (pinfunction "2_2") (pintype "passive"))
      (node (ref "U2") (pin "13") (pinfunction "AGND_13") (pintype "passive"))
      (node (ref "U2") (pin "24") (pinfunction "LED4/I2C_24") (pintype "passive"))
      (node (ref "U2") (pin "41") (pinfunction "EPAD_41") (pintype "passive"))
      (node (ref "U4") (pin "1") (pinfunction "VSS_1") (pintype "passive"))
      (node (ref "ZD1") (pin "1") (pinfunction "A_1") (pintype "passive"))
    )
    (net (code "43") (name "Net-(D1-A)") (class "Default")
      (node (ref "D1") (pin "1") (pinfunction "A_1") (pintype "passive"))
      (node (ref "R13") (pin "1") (pinfunction "1_1") (pintype "passive"))
    )
    (net (code "44") (name "Net-(D2-K)") (class "Default")
      (node (ref "D2") (pin "2") (pinfunction "K_2") (pintype "passive"))
      (node (ref "R14") (pin "1") (pinfunction "1_1") (pintype "passive"))
    )
    (net (code "45") (name "Net-(D3-Pad3)") (class "Default")
      (node (ref "D3") (pin "3") (pintype "passive"))
      (node (ref "R15") (pin "2") (pinfunction "2_2") (pintype "passive"))
    )
    (net (code "46") (name "Net-(J5-DM)") (class "Default")
      (node (ref "J5") (pin "2") (pinfunction "DM_2") (pintype "passive"))
      (node (ref "J5") (pin "3") (pinfunction "DP_3") (pintype "passive"))
    )
    (net (code "47") (name "Net-(J5-GND)") (class "Default")
      (node (ref "J5") (pin "4") (pinfunction "GND_4") (pintype "passive"))
      (node (ref "R16") (pin "2") (pinfunction "2_2") (pintype "passive"))
      (node (ref "R28") (pin "2") (pinfunction "2_2") (pintype "passive"))
    )
    (net (code "48") (name "Net-(J5-VBUS)") (class "Default")
      (node (ref "C22") (pin "2") (pinfunction "2_2") (pintype "passive"))
      (node (ref "J5") (pin "1") (pinfunction "VBUS_1") (pintype "passive"))
      (node (ref "Q10") (pin "3") (pinfunction "D_3") (pintype "passive"))
      (node (ref "R17") (pin "1") (pinfunction "1_1") (pintype "passive"))
      (node (ref "R18") (pin "2") (pinfunction "2_2") (pintype "passive"))
    )
    (net (code "49") (name "Net-(J6-Pad1)") (class "Default")
      (node (ref "J6") (pin "1") (pinfunction "1_1") (pintype "passive"))
      (node (ref "R23") (pin "1") (pinfunction "1_1") (pintype "passive"))
    )
    (net (code "50") (name "Net-(J6-Pad2)") (class "Default")
      (node (ref "J6") (pin "2") (pinfunction "2_2") (pintype "passive"))
      (node (ref "R24") (pin "1") (pinfunction "1_1") (pintype "passive"))
    )
    (net (code "51") (name "Net-(J6-Pad3)") (class "Default")
      (node (ref "J6") (pin "3") (pinfunction "3_3") (pintype "passive"))
      (node (ref "R25") (pin "1") (pinfunction "1_1") (pintype "passive"))
    )
    (net (code "52") (name "Net-(J6-Pad4)") (class "Default")
      (node (ref "J6") (pin "4") (pinfunction "4_4") (pintype "passive"))
      (node (ref "R26") (pin "1") (pinfunction "1_1") (pintype "passive"))
    )
    (net (code "53") (name "Net-(J6-Pad5)") (class "Default")
      (node (ref "J6") (pin "5") (pinfunction "5_5") (pintype "passive"))
      (node (ref "R29") (pin "1") (pinfunction "1_1") (pintype "passive"))
    )
    (net (code "54") (name "Net-(J6-Pad6)") (class "Default")
      (node (ref "J6") (pin "6") (pinfunction "6_6") (pintype "passive"))
      (node (ref "R30") (pin "1") (pinfunction "1_1") (pintype "passive"))
    )
    (net (code "55") (name "Net-(Q1-D1)") (class "Default")
      (node (ref "Q1") (pin "2") (pinfunction "D1_2") (pintype "passive"))
      (node (ref "Q2") (pin "5") (pinfunction "D2_5") (pintype "passive"))
    )
    (net (code "56") (name "Net-(Q1-G1)") (class "Default")
      (node (ref "Q1") (pin "6") (pinfunction "G1_6") (pintype "passive"))
      (node (ref "Q2") (pin "6") (pinfunction "G1_6") (pintype "passive"))
      (node (ref "Q3") (pin "6") (pinfunction "G1_6") (pintype "passive"))
      (node (ref "Q4") (pin "6") (pinfunction "G1_6") (pintype "passive"))
      (node (ref "U1") (pin "1") (pinfunction "OD_1") (pintype "passive"))
    )
    (net (code "57") (name "Net-(Q1-G2)") (class "Default")
      (node (ref "Q1") (pin "4") (pinfunction "G2_4") (pintype "passive"))
      (node (ref "Q2") (pin "4") (pinfunction "G2_4") (pintype "passive"))
      (node (ref "Q3") (pin "4") (pinfunction "G2_4") (pintype "passive"))
      (node (ref "Q4") (pin "4") (pinfunction "G2_4") (pintype "passive"))
      (node (ref "U1") (pin "3") (pinfunction "OC_3") (pintype "passive"))
    )
    (net (code "58") (name "Net-(Q2-D1)") (class "Default")
      (node (ref "Q2") (pin "2") (pinfunction "D1_2") (pintype "passive"))
      (node (ref "Q3") (pin "5") (pinfunction "D2_5") (pintype "passive"))
    )
    (net (code "59") (name "Net-(Q3-D1)") (class "Default")
      (node (ref "Q3") (pin "2") (pinfunction "D1_2") (pintype "passive"))
      (node (ref "Q4") (pin "5") (pinfunction "D2_5") (pintype "passive"))
    )
    (net (code "60") (name "Net-(Q10-G)") (class "Default")
      (node (ref "Q10") (pin "1") (pinfunction "G_1") (pintype "passive"))
      (node (ref "Q11") (pin "3") (pinfunction "D_3") (pintype "passive"))
      (node (ref "Q12") (pin "1") (pinfunction "G_1") (pintype "passive"))
      (node (ref "R31") (pin "1") (pinfunction "1_1") (pintype "passive"))
    )
    (net (code "61") (name "Net-(Q11-G)") (class "Default")
      (node (ref "Q11") (pin "1") (pinfunction "G_1") (pintype "passive"))
      (node (ref "R27") (pin "2") (pinfunction "2_2") (pintype "passive"))
      (node (ref "R33") (pin "1") (pinfunction "1_1") (pintype "passive"))
    )
    (net (code "62") (name "Net-(Q12-S)") (class "Default")
      (node (ref "Q12") (pin "2") (pinfunction "S_2") (pintype "passive"))
      (node (ref "R17") (pin "2") (pinfunction "2_2") (pintype "passive"))
    )
    (net (code "63") (name "Net-(U1-CS)") (class "Default")
      (node (ref "R2") (pin "2") (pinfunction "2_2") (pintype "passive"))
      (node (ref "U1") (pin "2") (pinfunction "CS_2") (pintype "passive"))
    )
    (net (code "64") (name "Net-(U1-VCC)") (class "Default")
      (node (ref "C1") (pin "2") (pinfunction "2_2") (pintype "passive"))
      (node (ref "R1") (pin "1") (pinfunction "1_1") (pintype "passive"))
      (node (ref "U1") (pin "5") (pinfunction "VCC_5") (pintype "passive"))
    )
    (net (code "65") (name "unconnected-(J4-SBU1-PadA8)") (class "Default")
      (node (ref "J4") (pin "A8") (pinfunction "SBU1_A8") (pintype "passive"))
    )
    (net (code "66") (name "unconnected-(J4-SBU2-PadB8)") (class "Default")
      (node (ref "J4") (pin "B8") (pinfunction "SBU2_B8") (pintype "passive"))
    )
    (net (code "67") (name "unconnected-(J4-SSRXn1-PadB10)") (class "Default")
      (node (ref "J4") (pin "B10") (pinfunction "SSRXn1_B10") (pintype "passive"))
    )
    (net (code "68") (name "unconnected-(J4-SSRXn2-PadA10)") (class "Default")
      (node (ref "J4") (pin "A10") (pinfunction "SSRXn2_A10") (pintype "passive"))
    )
    (net (code "69") (name "unconnected-(J4-SSRXp1-PadB11)") (class "Default")
      (node (ref "J4") (pin "B11") (pinfunction "SSRXp1_B11") (pintype "passive"))
    )
    (net (code "70") (name "unconnected-(J4-SSRXp2-PadA11)") (class "Default")
      (node (ref "J4") (pin "A11") (pinfunction "SSRXp2_A11") (pintype "passive"))
    )
    (net (code "71") (name "unconnected-(J4-SSTXn1-PadA3)") (class "Default")
      (node (ref "J4") (pin "A3") (pinfunction "SSTXn1_A3") (pintype "passive"))
    )
    (net (code "72") (name "unconnected-(J4-SSTXn2-PadB3)") (class "Default")
      (node (ref "J4") (pin "B3") (pinfunction "SSTXn2_B3") (pintype "passive"))
    )
    (net (code "73") (name "unconnected-(J4-SSTXp1-PadA2)") (class "Default")
      (node (ref "J4") (pin "A2") (pinfunction "SSTXp1_A2") (pintype "passive"))
    )
    (net (code "74") (name "unconnected-(J4-SSTXp2-PadB2)") (class "Default")
      (node (ref "J4") (pin "B2") (pinfunction "SSTXp2_B2") (pintype "passive"))
    )
    (net (code "75") (name "unconnected-(J5-SHIELD1-Pad5)") (class "Default")
      (node (ref "J5") (pin "5") (pinfunction "SHIELD1_5") (pintype "passive"))
    )
    (net (code "76") (name "unconnected-(J5-SHIELD2-Pad6)") (class "Default")
      (node (ref "J5") (pin "6") (pinfunction "SHIELD2_6") (pintype "passive"))
    )
    (net (code "77") (name "unconnected-(Q1-D2-Pad5)") (class "Default")
      (node (ref "Q1") (pin "5") (pinfunction "D2_5") (pintype "passive"))
    )
    (net (code "78") (name "unconnected-(Q4-D1-Pad2)") (class "Default")
      (node (ref "Q4") (pin "2") (pinfunction "D1_2") (pintype "passive"))
    )
    (net (code "79") (name "unconnected-(Q5-D1-Pad2)") (class "Default")
      (node (ref "Q5") (pin "2") (pinfunction "D1_2") (pintype "passive"))
    )
    (net (code "80") (name "unconnected-(Q6-D1-Pad2)") (class "Default")
      (node (ref "Q6") (pin "2") (pinfunction "D1_2") (pintype "passive"))
    )
    (net (code "81") (name "unconnected-(Q8-D1-Pad2)") (class "Default")
      (node (ref "Q8") (pin "2") (pinfunction "D1_2") (pintype "passive"))
    )
    (net (code "82") (name "unconnected-(U1-TD-Pad4)") (class "Default")
      (node (ref "U1") (pin "4") (pinfunction "TD_4") (pintype "passive"))
    )
    (net (code "83") (name "unconnected-(U4-PA2-Pad4)") (class "Default")
      (node (ref "U4") (pin "4") (pinfunction "PA2_4") (pintype "passive"))
    )
    (net (code "84") (name "unconnected-(U4-PB3-Pad9)") (class "Default")
      (node (ref "U4") (pin "9") (pinfunction "PB3_9") (pintype "passive"))
    )
  )
)
